# MDAS_Controller_V1_test.net
KiCad netlist of a schematic drawn in EAGLE
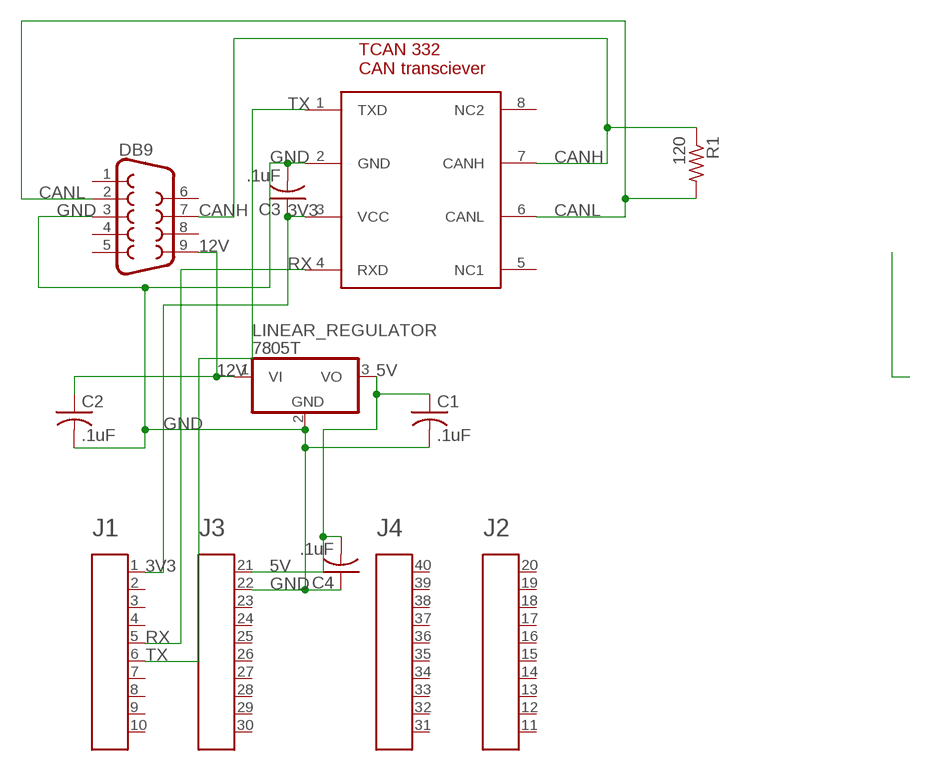
[diagram p0: schematic, sheet 1]

(export (version "E")
  (design (tool "Eeschema 10.0.6"))
  (components
    (comp (ref "A1")
      (value "HEADER4X10-BOOSTERPACK")
      (footprint "eagle-import:4X10-BOOSTERPACK")
      (libsource (lib "eagle-import") (part "HEADER4X10-BOOSTERPACK"))
    )
    (comp (ref "C1")
      (value ".1uF")
      (footprint "eagle-import:C0603")
      (libsource (lib "eagle-import") (part "C-USC0603"))
    )
    (comp (ref "C2")
      (value ".1uF")
      (footprint "eagle-import:C0603")
      (libsource (lib "eagle-import") (part "C-USC0603"))
    )
    (comp (ref "C3")
      (value ".1uF")
      (footprint "eagle-import:C0603")
      (libsource (lib "eagle-import") (part "C-USC0603"))
    )
    (comp (ref "C4")
      (value ".1uF")
      (footprint "eagle-import:C0603")
      (libsource (lib "eagle-import") (part "C-USC0603"))
    )
    (comp (ref "CAN_TRANSCIEVER")
      (value "TCAN332")
      (footprint "eagle-import:SOIC127P600X172-8N")
      (libsource (lib "eagle-import") (part "TCAN332"))
    )
    (comp (ref "DB9")
      (value "DB9FEMALE")
      (footprint "eagle-import:DB9")
      (libsource (lib "eagle-import") (part "DB9FEMALE"))
    )
    (comp (ref "LINEAR_REGULATOR")
      (value "7805T")
      (footprint "eagle-import:TO220H")
      (libsource (lib "eagle-import") (part "78T05"))
    )
    (comp (ref "R1")
      (value "120")
      (footprint "eagle-import:0207_10")
      (libsource (lib "eagle-import") (part "R-US_0207/10"))
    )
  )
  (nets
    (net (code "1") (name "/3V3") (class "Default")
      (node (ref "A1") (pin "1") (pinfunction "P$1_1") (pintype "bidirectional"))
      (node (ref "C3") (pin "1") (pinfunction "1_1") (pintype "passive"))
      (node (ref "CAN_TRANSCIEVER") (pin "3") (pinfunction "VCC_3") (pintype "bidirectional"))
    )
    (net (code "2") (name "/5V") (class "Default")
      (node (ref "A1") (pin "21") (pinfunction "P$21_21") (pintype "bidirectional"))
      (node (ref "C1") (pin "1") (pinfunction "1_1") (pintype "passive"))
      (node (ref "C4") (pin "2") (pinfunction "2_2") (pintype "passive"))
      (node (ref "LINEAR_REGULATOR") (pin "3") (pinfunction "VO_3") (pintype "passive"))
    )
    (net (code "3") (name "/12V") (class "Default")
      (node (ref "C2") (pin "1") (pinfunction "1_1") (pintype "passive"))
      (node (ref "DB9") (pin "9") (pinfunction "9_9") (pintype "passive"))
      (node (ref "LINEAR_REGULATOR") (pin "1") (pinfunction "VI_1") (pintype "input"))
    )
    (net (code "4") (name "/CANH") (class "Default")
      (node (ref "CAN_TRANSCIEVER") (pin "7") (pinfunction "CANH_7") (pintype "bidirectional"))
      (node (ref "DB9") (pin "7") (pinfunction "7_7") (pintype "passive"))
      (node (ref "R1") (pin "1") (pinfunction "1_1") (pintype "passive"))
    )
    (net (code "5") (name "/CANL") (class "Default")
      (node (ref "CAN_TRANSCIEVER") (pin "6") (pinfunction "CANL_6") (pintype "bidirectional"))
      (node (ref "DB9") (pin "2") (pinfunction "2_2") (pintype "passive"))
      (node (ref "R1") (pin "2") (pinfunction "2_2") (pintype "passive"))
    )
    (net (code "6") (name "/GND") (class "Default")
      (node (ref "A1") (pin "22") (pinfunction "P$22_22") (pintype "bidirectional"))
      (node (ref "C1") (pin "2") (pinfunction "2_2") (pintype "passive"))
      (node (ref "C2") (pin "2") (pinfunction "2_2") (pintype "passive"))
      (node (ref "C3") (pin "2") (pinfunction "2_2") (pintype "passive"))
      (node (ref "C4") (pin "1") (pinfunction "1_1") (pintype "passive"))
      (node (ref "CAN_TRANSCIEVER") (pin "2") (pinfunction "GND_2") (pintype "bidirectional"))
      (node (ref "DB9") (pin "3") (pinfunction "3_3") (pintype "passive"))
      (node (ref "LINEAR_REGULATOR") (pin "2") (pinfunction "GND_2") (pintype "passive"))
    )
    (net (code "7") (name "/RX") (class "Default")
      (node (ref "A1") (pin "5") (pinfunction "P$5_5") (pintype "bidirectional"))
      (node (ref "CAN_TRANSCIEVER") (pin "4") (pinfunction "RXD_4") (pintype "bidirectional"))
    )
    (net (code "8") (name "/TX") (class "Default")
      (node (ref "A1") (pin "6") (pinfunction "P$6_6") (pintype "bidirectional"))
      (node (ref "CAN_TRANSCIEVER") (pin "1") (pinfunction "TXD_1") (pintype "bidirectional"))
    )
    (net (code "9") (name "unconnected-(A1-P$2-Pad2)") (class "Default")
      (node (ref "A1") (pin "2") (pinfunction "P$2_2") (pintype "bidirectional"))
    )
    (net (code "10") (name "unconnected-(A1-P$3-Pad3)") (class "Default")
      (node (ref "A1") (pin "3") (pinfunction "P$3_3") (pintype "bidirectional"))
    )
    (net (code "11") (name "unconnected-(A1-P$4-Pad4)") (class "Default")
      (node (ref "A1") (pin "4") (pinfunction "P$4_4") (pintype "bidirectional"))
    )
    (net (code "12") (name "unconnected-(A1-P$7-Pad7)") (class "Default")
      (node (ref "A1") (pin "7") (pinfunction "P$7_7") (pintype "bidirectional"))
    )
    (net (code "13") (name "unconnected-(A1-P$8-Pad8)") (class "Default")
      (node (ref "A1") (pin "8") (pinfunction "P$8_8") (pintype "bidirectional"))
    )
    (net (code "14") (name "unconnected-(A1-P$9-Pad9)") (class "Default")
      (node (ref "A1") (pin "9") (pinfunction "P$9_9") (pintype "bidirectional"))
    )
    (net (code "15") (name "unconnected-(A1-P$10-Pad10)") (class "Default")
      (node (ref "A1") (pin "10") (pinfunction "P$10_10") (pintype "bidirectional"))
    )
    (net (code "16") (name "unconnected-(A1-P$11-Pad11)") (class "Default")
      (node (ref "A1") (pin "11") (pinfunction "P$11_11") (pintype "bidirectional"))
    )
    (net (code "17") (name "unconnected-(A1-P$12-Pad12)") (class "Default")
      (node (ref "A1") (pin "12") (pinfunction "P$12_12") (pintype "bidirectional"))
    )
    (net (code "18") (name "unconnected-(A1-P$13-Pad13)") (class "Default")
      (node (ref "A1") (pin "13") (pinfunction "P$13_13") (pintype "bidirectional"))
    )
    (net (code "19") (name "unconnected-(A1-P$14-Pad14)") (class "Default")
      (node (ref "A1") (pin "14") (pinfunction "P$14_14") (pintype "bidirectional"))
    )
    (net (code "20") (name "unconnected-(A1-P$15-Pad15)") (class "Default")
      (node (ref "A1") (pin "15") (pinfunction "P$15_15") (pintype "bidirectional"))
    )
    (net (code "21") (name "unconnected-(A1-P$16-Pad16)") (class "Default")
      (node (ref "A1") (pin "16") (pinfunction "P$16_16") (pintype "bidirectional"))
    )
    (net (code "22") (name "unconnected-(A1-P$17-Pad17)") (class "Default")
      (node (ref "A1") (pin "17") (pinfunction "P$17_17") (pintype "bidirectional"))
    )
    (net (code "23") (name "unconnected-(A1-P$18-Pad18)") (class "Default")
      (node (ref "A1") (pin "18") (pinfunction "P$18_18") (pintype "bidirectional"))
    )
    (net (code "24") (name "unconnected-(A1-P$19-Pad19)") (class "Default")
      (node (ref "A1") (pin "19") (pinfunction "P$19_19") (pintype "bidirectional"))
    )
    (net (code "25") (name "unconnected-(A1-P$20-Pad20)") (class "Default")
      (node (ref "A1") (pin "20") (pinfunction "P$20_20") (pintype "bidirectional"))
    )
    (net (code "26") (name "unconnected-(A1-P$23-Pad23)") (class "Default")
      (node (ref "A1") (pin "23") (pinfunction "P$23_23") (pintype "bidirectional"))
    )
    (net (code "27") (name "unconnected-(A1-P$24-Pad24)") (class "Default")
      (node (ref "A1") (pin "24") (pinfunction "P$24_24") (pintype "bidirectional"))
    )
    (net (code "28") (name "unconnected-(A1-P$25-Pad25)") (class "Default")
      (node (ref "A1") (pin "25") (pinfunction "P$25_25") (pintype "bidirectional"))
    )
    (net (code "29") (name "unconnected-(A1-P$26-Pad26)") (class "Default")
      (node (ref "A1") (pin "26") (pinfunction "P$26_26") (pintype "bidirectional"))
    )
    (net (code "30") (name "unconnected-(A1-P$27-Pad27)") (class "Default")
      (node (ref "A1") (pin "27") (pinfunction "P$27_27") (pintype "bidirectional"))
    )
    (net (code "31") (name "unconnected-(A1-P$28-Pad28)") (class "Default")
      (node (ref "A1") (pin "28") (pinfunction "P$28_28") (pintype "bidirectional"))
    )
    (net (code "32") (name "unconnected-(A1-P$29-Pad29)") (class "Default")
      (node (ref "A1") (pin "29") (pinfunction "P$29_29") (pintype "bidirectional"))
    )
    (net (code "33") (name "unconnected-(A1-P$30-Pad30)") (class "Default")
      (node (ref "A1") (pin "30") (pinfunction "P$30_30") (pintype "bidirectional"))
    )
    (net (code "34") (name "unconnected-(A1-P$31-Pad31)") (class "Default")
      (node (ref "A1") (pin "31") (pinfunction "P$31_31") (pintype "bidirectional"))
    )
    (net (code "35") (name "unconnected-(A1-P$32-Pad32)") (class "Default")
      (node (ref "A1") (pin "32") (pinfunction "P$32_32") (pintype "bidirectional"))
    )
    (net (code "36") (name "unconnected-(A1-P$33-Pad33)") (class "Default")
      (node (ref "A1") (pin "33") (pinfunction "P$33_33") (pintype "bidirectional"))
    )
    (net (code "37") (name "unconnected-(A1-P$34-Pad34)") (class "Default")
      (node (ref "A1") (pin "34") (pinfunction "P$34_34") (pintype "bidirectional"))
    )
    (net (code "38") (name "unconnected-(A1-P$35-Pad35)") (class "Default")
      (node (ref "A1") (pin "35") (pinfunction "P$35_35") (pintype "bidirectional"))
    )
    (net (code "39") (name "unconnected-(A1-P$36-Pad36)") (class "Default")
      (node (ref "A1") (pin "36") (pinfunction "P$36_36") (pintype "bidirectional"))
    )
    (net (code "40") (name "unconnected-(A1-P$37-Pad37)") (class "Default")
      (node (ref "A1") (pin "37") (pinfunction "P$37_37") (pintype "bidirectional"))
    )
    (net (code "41") (name "unconnected-(A1-P$38-Pad38)") (class "Default")
      (node (ref "A1") (pin "38") (pinfunction "P$38_38") (pintype "bidirectional"))
    )
    (net (code "42") (name "unconnected-(A1-P$39-Pad39)") (class "Default")
      (node (ref "A1") (pin "39") (pinfunction "P$39_39") (pintype "bidirectional"))
    )
    (net (code "43") (name "unconnected-(A1-P$40-Pad40)") (class "Default")
      (node (ref "A1") (pin "40") (pinfunction "P$40_40") (pintype "bidirectional"))
    )
    (net (code "44") (name "unconnected-(CAN_TRANSCIEVER-NC1-Pad5)") (class "Default")
      (node (ref "CAN_TRANSCIEVER") (pin "5") (pinfunction "NC1_5") (pintype "bidirectional"))
    )
    (net (code "45") (name "unconnected-(CAN_TRANSCIEVER-NC2-Pad8)") (class "Default")
      (node (ref "CAN_TRANSCIEVER") (pin "8") (pinfunction "NC2_8") (pintype "bidirectional"))
    )
    (net (code "46") (name "unconnected-(DB9-Pad1)") (class "Default")
      (node (ref "DB9") (pin "1") (pinfunction "1_1") (pintype "passive"))
    )
    (net (code "47") (name "unconnected-(DB9-Pad4)") (class "Default")
      (node (ref "DB9") (pin "4") (pinfunction "4_4") (pintype "passive"))
    )
    (net (code "48") (name "unconnected-(DB9-Pad5)") (class "Default")
      (node (ref "DB9") (pin "5") (pinfunction "5_5") (pintype "passive"))
    )
    (net (code "49") (name "unconnected-(DB9-Pad6)") (class "Default")
      (node (ref "DB9") (pin "6") (pinfunction "6_6") (pintype "passive"))
    )
    (net (code "50") (name "unconnected-(DB9-Pad8)") (class "Default")
      (node (ref "DB9") (pin "8") (pinfunction "8_8") (pintype "passive"))
    )
  )
)
